# Hormann_EE000591_reveng_schematic.net
KiCad netlist of a schematic drawn in EAGLE
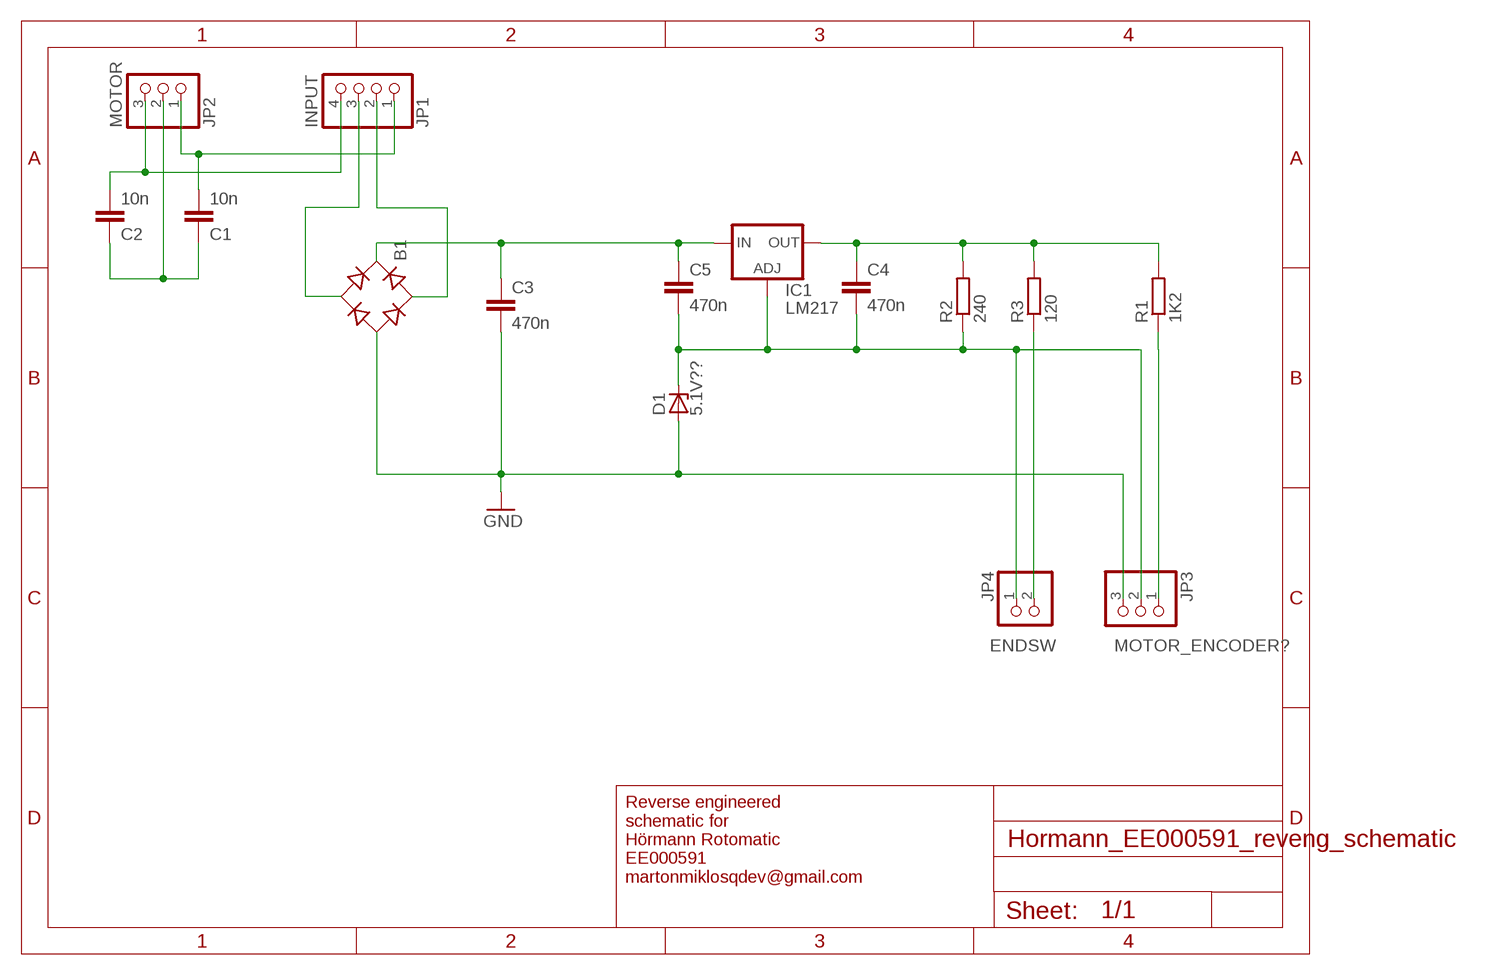
[diagram p0: schematic, sheet 1]

(export (version "E")
  (design (tool "Eeschema 10.0.6"))
  (components
    (comp (ref "B1")
      (value "DBLS209G")
      (footprint "eagle-import:DBS")
      (libsource (lib "eagle-import") (part "DB?GLS209"))
    )
    (comp (ref "C1")
      (value "10n")
      (footprint "eagle-import:C025-025X050")
      (libsource (lib "eagle-import") (part "C-EU025-025X050"))
    )
    (comp (ref "C2")
      (value "10n")
      (footprint "eagle-import:C025-025X050")
      (libsource (lib "eagle-import") (part "C-EU025-025X050"))
    )
    (comp (ref "C3")
      (value "470n")
      (footprint "eagle-import:C025-030X050")
      (libsource (lib "eagle-import") (part "C-EU025-030X050"))
    )
    (comp (ref "C4")
      (value "470n")
      (footprint "eagle-import:C025-030X050")
      (libsource (lib "eagle-import") (part "C-EU025-030X050"))
    )
    (comp (ref "C5")
      (value "470n")
      (footprint "eagle-import:C025-030X050")
      (libsource (lib "eagle-import") (part "C-EU025-030X050"))
    )
    (comp (ref "D1")
      (value "5.1V??")
      (footprint "eagle-import:DO34Z7")
      (libsource (lib "eagle-import") (part "ZENER-DIODEDO34-7"))
    )
    (comp (ref "IC1")
      (value "LM217")
      (footprint "eagle-import:317TL")
      (libsource (lib "eagle-import") (part "LM317TL"))
    )
    (comp (ref "JP1")
      (value "INPUT")
      (footprint "eagle-import:1X04")
      (libsource (lib "eagle-import") (part "PINHD-1X4"))
    )
    (comp (ref "JP2")
      (value "MOTOR")
      (footprint "eagle-import:1X03")
      (libsource (lib "eagle-import") (part "PINHD-1X3"))
    )
    (comp (ref "JP3")
      (value "MOTOR_ENCODER?")
      (footprint "eagle-import:1X03")
      (libsource (lib "eagle-import") (part "PINHD-1X3"))
    )
    (comp (ref "JP4")
      (value "ENDSW")
      (footprint "eagle-import:1X02")
      (libsource (lib "eagle-import") (part "PINHD-1X2"))
    )
    (comp (ref "R1")
      (value "1K2")
      (footprint "eagle-import:0207_10")
      (libsource (lib "eagle-import") (part "R-EU_0207/10"))
    )
    (comp (ref "R2")
      (value "240")
      (footprint "eagle-import:0207_10")
      (libsource (lib "eagle-import") (part "R-EU_0207/10"))
    )
    (comp (ref "R3")
      (value "120")
      (footprint "eagle-import:0207_10")
      (libsource (lib "eagle-import") (part "R-EU_0207/10"))
    )
  )
  (nets
    (net (code "1") (name "GND") (class "Default")
      (node (ref "B1") (pin "-") (pinfunction "-_-") (pintype "passive"))
      (node (ref "C3") (pin "2") (pinfunction "2_2") (pintype "passive"))
      (node (ref "D1") (pin "A") (pinfunction "A_A") (pintype "passive"))
      (node (ref "JP3") (pin "3") (pinfunction "3_3") (pintype "passive"))
    )
    (net (code "2") (name "Net-(B1-PadAC1)") (class "Default")
      (node (ref "B1") (pin "AC1") (pinfunction "AC1_AC1") (pintype "passive"))
      (node (ref "JP1") (pin "2") (pinfunction "2_2") (pintype "passive"))
    )
    (net (code "3") (name "Net-(B1-PadAC2)") (class "Default")
      (node (ref "B1") (pin "AC2") (pinfunction "AC2_AC2") (pintype "passive"))
      (node (ref "JP1") (pin "3") (pinfunction "3_3") (pintype "passive"))
    )
    (net (code "4") (name "Net-(C1-Pad1)") (class "Default")
      (node (ref "C1") (pin "1") (pinfunction "1_1") (pintype "passive"))
      (node (ref "C2") (pin "1") (pinfunction "1_1") (pintype "passive"))
      (node (ref "JP2") (pin "2") (pinfunction "2_2") (pintype "passive"))
    )
    (net (code "5") (name "Net-(C1-Pad2)") (class "Default")
      (node (ref "C1") (pin "2") (pinfunction "2_2") (pintype "passive"))
      (node (ref "JP1") (pin "1") (pinfunction "1_1") (pintype "passive"))
      (node (ref "JP2") (pin "1") (pinfunction "1_1") (pintype "passive"))
    )
    (net (code "6") (name "Net-(C2-Pad2)") (class "Default")
      (node (ref "C2") (pin "2") (pinfunction "2_2") (pintype "passive"))
      (node (ref "JP1") (pin "4") (pinfunction "4_4") (pintype "passive"))
      (node (ref "JP2") (pin "3") (pinfunction "3_3") (pintype "passive"))
    )
    (net (code "7") (name "Net-(IC1-ADJ)") (class "Default")
      (node (ref "C4") (pin "2") (pinfunction "2_2") (pintype "passive"))
      (node (ref "C5") (pin "2") (pinfunction "2_2") (pintype "passive"))
      (node (ref "D1") (pin "C") (pinfunction "C_C") (pintype "passive"))
      (node (ref "IC1") (pin "1") (pinfunction "ADJ_1") (pintype "input"))
      (node (ref "JP3") (pin "2") (pinfunction "2_2") (pintype "passive"))
      (node (ref "JP4") (pin "1") (pinfunction "1_1") (pintype "passive"))
      (node (ref "R2") (pin "1") (pinfunction "1_1") (pintype "passive"))
    )
    (net (code "8") (name "Net-(IC1-IN)") (class "Default")
      (node (ref "B1") (pin "+") (pinfunction "+_+") (pintype "passive"))
      (node (ref "C3") (pin "1") (pinfunction "1_1") (pintype "passive"))
      (node (ref "C5") (pin "1") (pinfunction "1_1") (pintype "passive"))
      (node (ref "IC1") (pin "3") (pinfunction "IN_3") (pintype "input"))
    )
    (net (code "9") (name "Net-(IC1-OUT)") (class "Default")
      (node (ref "C4") (pin "1") (pinfunction "1_1") (pintype "passive"))
      (node (ref "IC1") (pin "2") (pinfunction "OUT_2") (pintype "passive"))
      (node (ref "R1") (pin "2") (pinfunction "2_2") (pintype "passive"))
      (node (ref "R2") (pin "2") (pinfunction "2_2") (pintype "passive"))
      (node (ref "R3") (pin "2") (pinfunction "2_2") (pintype "passive"))
    )
    (net (code "10") (name "Net-(JP3-Pad1)") (class "Default")
      (node (ref "JP3") (pin "1") (pinfunction "1_1") (pintype "passive"))
      (node (ref "R1") (pin "1") (pinfunction "1_1") (pintype "passive"))
    )
    (net (code "11") (name "Net-(JP4-Pad2)") (class "Default")
      (node (ref "JP4") (pin "2") (pinfunction "2_2") (pintype "passive"))
      (node (ref "R3") (pin "1") (pinfunction "1_1") (pintype "passive"))
    )
  )
)
